# Optocoupler_STM32.net
KiCad netlist of a schematic drawn in Altium Designer
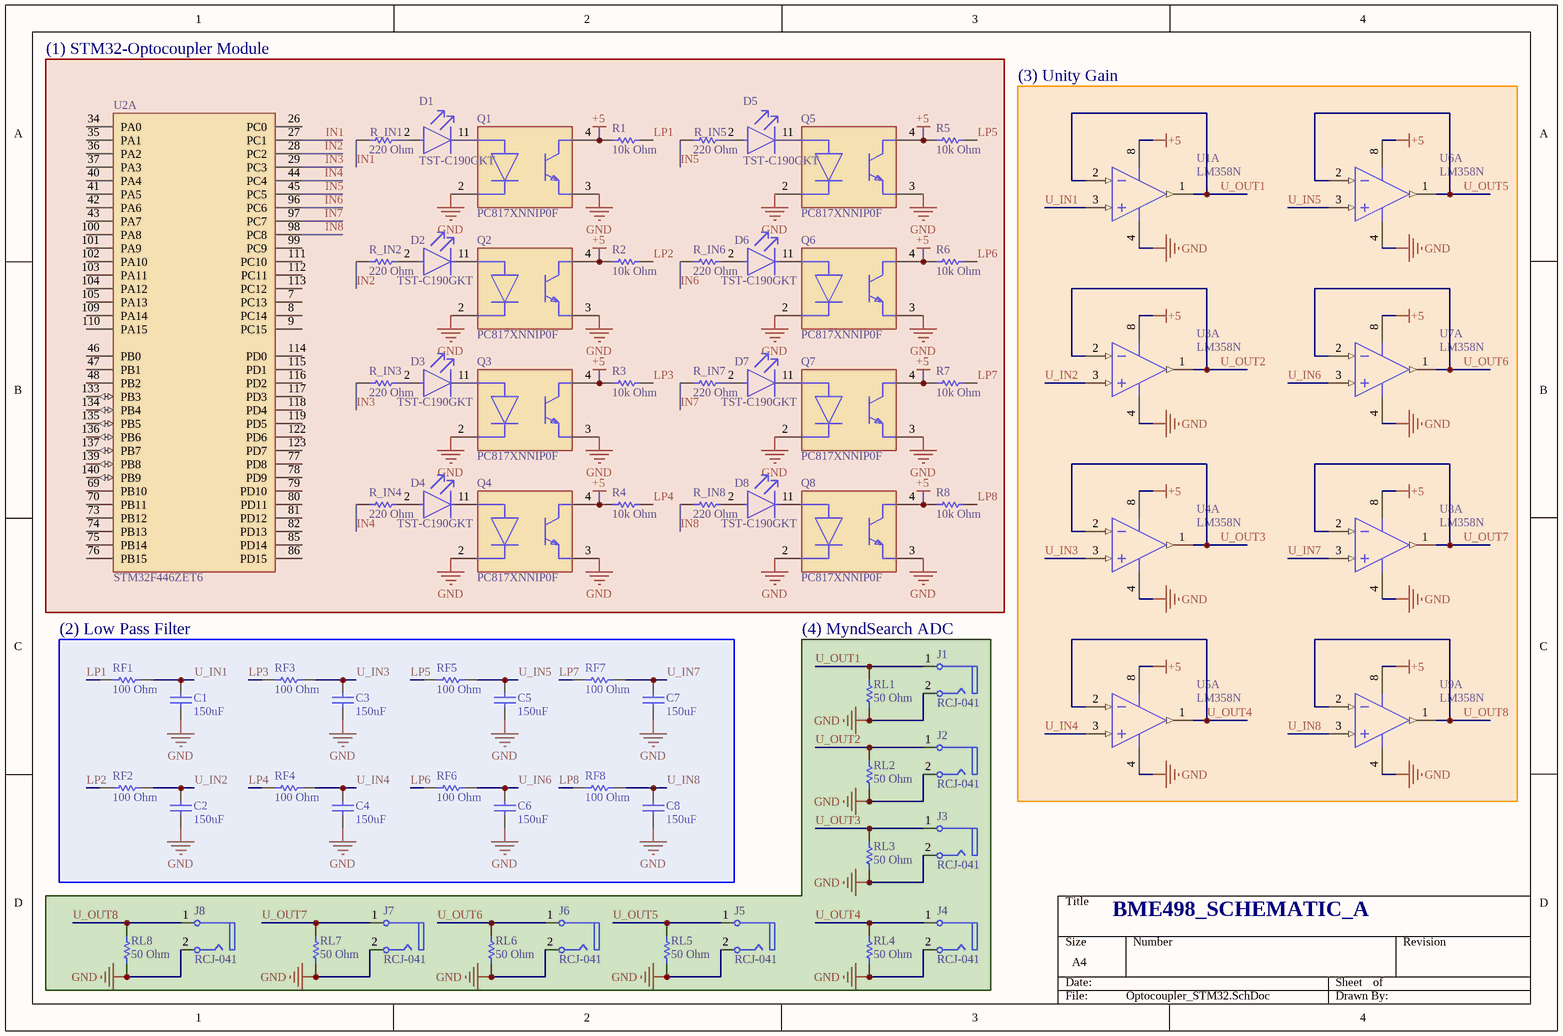
[diagram p0: Optocoupler_STM32.SchDoc]

(export (version "E")
  (design (tool "Eeschema 10.0.6"))
  (components
    (comp (ref "C1")
      (value "150uF")
      (footprint "RADIAL-0.1")
      (description "Capacitor")
      (fields
        (field (name "MANUFACTURER PART NUMBER") "EEA-GA1C150B")
        (field (name "PUBLISHER") "Altium Limited")
      )
      (libsource (lib "ECE295-Capacitors-TH") (part "CAP ALUM 15UF 20% 16V RADIAL"))
    )
    (comp (ref "C2")
      (value "150uF")
      (footprint "RADIAL-0.1")
      (description "Capacitor")
      (fields
        (field (name "MANUFACTURER PART NUMBER") "EEA-GA1C150B")
        (field (name "PUBLISHER") "Altium Limited")
      )
      (libsource (lib "ECE295-Capacitors-TH") (part "CAP ALUM 15UF 20% 16V RADIAL"))
    )
    (comp (ref "C3")
      (value "150uF")
      (footprint "RADIAL-0.1")
      (description "Capacitor")
      (fields
        (field (name "MANUFACTURER PART NUMBER") "EEA-GA1C150B")
        (field (name "PUBLISHER") "Altium Limited")
      )
      (libsource (lib "ECE295-Capacitors-TH") (part "CAP ALUM 15UF 20% 16V RADIAL"))
    )
    (comp (ref "C4")
      (value "150uF")
      (footprint "RADIAL-0.1")
      (description "Capacitor")
      (fields
        (field (name "MANUFACTURER PART NUMBER") "EEA-GA1C150B")
        (field (name "PUBLISHER") "Altium Limited")
      )
      (libsource (lib "ECE295-Capacitors-TH") (part "CAP ALUM 15UF 20% 16V RADIAL"))
    )
    (comp (ref "C5")
      (value "150uF")
      (footprint "RADIAL-0.1")
      (description "Capacitor")
      (fields
        (field (name "MANUFACTURER PART NUMBER") "EEA-GA1C150B")
        (field (name "PUBLISHER") "Altium Limited")
      )
      (libsource (lib "ECE295-Capacitors-TH") (part "CAP ALUM 15UF 20% 16V RADIAL"))
    )
    (comp (ref "C6")
      (value "150uF")
      (footprint "RADIAL-0.1")
      (description "Capacitor")
      (fields
        (field (name "MANUFACTURER PART NUMBER") "EEA-GA1C150B")
        (field (name "PUBLISHER") "Altium Limited")
      )
      (libsource (lib "ECE295-Capacitors-TH") (part "CAP ALUM 15UF 20% 16V RADIAL"))
    )
    (comp (ref "C7")
      (value "150uF")
      (footprint "RADIAL-0.1")
      (description "Capacitor")
      (fields
        (field (name "MANUFACTURER PART NUMBER") "EEA-GA1C150B")
        (field (name "PUBLISHER") "Altium Limited")
      )
      (libsource (lib "ECE295-Capacitors-TH") (part "CAP ALUM 15UF 20% 16V RADIAL"))
    )
    (comp (ref "C8")
      (value "150uF")
      (footprint "RADIAL-0.1")
      (description "Capacitor")
      (fields
        (field (name "MANUFACTURER PART NUMBER") "EEA-GA1C150B")
        (field (name "PUBLISHER") "Altium Limited")
      )
      (libsource (lib "ECE295-Capacitors-TH") (part "CAP ALUM 15UF 20% 16V RADIAL"))
    )
    (comp (ref "D1")
      (value "TST-C190GKT")
      (footprint "FP-LTST-C190GKT-MFG")
      (description "LED GREEN CLEAR CHIP SMD")
      (fields (field (name "VOLTAGE") "2V"))
      (libsource (lib "Altium Content Vault") (part "8706943c75ba83719d021d2fdc84c58"))
    )
    (comp (ref "D2")
      (value "TST-C190GKT")
      (footprint "FP-LTST-C190GKT-MFG")
      (description "LED GREEN CLEAR CHIP SMD")
      (fields (field (name "VOLTAGE") "2V"))
      (libsource (lib "Altium Content Vault") (part "8706943c75ba83719d021d2fdc84c58"))
    )
    (comp (ref "D3")
      (value "TST-C190GKT")
      (footprint "FP-LTST-C190GKT-MFG")
      (description "LED GREEN CLEAR CHIP SMD")
      (fields (field (name "VOLTAGE") "2V"))
      (libsource (lib "Altium Content Vault") (part "8706943c75ba83719d021d2fdc84c58"))
    )
    (comp (ref "D4")
      (value "TST-C190GKT")
      (footprint "FP-LTST-C190GKT-MFG")
      (description "LED GREEN CLEAR CHIP SMD")
      (fields (field (name "VOLTAGE") "2V"))
      (libsource (lib "Altium Content Vault") (part "8706943c75ba83719d021d2fdc84c58"))
    )
    (comp (ref "D5")
      (value "TST-C190GKT")
      (footprint "FP-LTST-C190GKT-MFG")
      (description "LED GREEN CLEAR CHIP SMD")
      (fields (field (name "VOLTAGE") "2V"))
      (libsource (lib "Altium Content Vault") (part "8706943c75ba83719d021d2fdc84c58"))
    )
    (comp (ref "D6")
      (value "TST-C190GKT")
      (footprint "FP-LTST-C190GKT-MFG")
      (description "LED GREEN CLEAR CHIP SMD")
      (fields (field (name "VOLTAGE") "2V"))
      (libsource (lib "Altium Content Vault") (part "8706943c75ba83719d021d2fdc84c58"))
    )
    (comp (ref "D7")
      (value "TST-C190GKT")
      (footprint "FP-LTST-C190GKT-MFG")
      (description "LED GREEN CLEAR CHIP SMD")
      (fields (field (name "VOLTAGE") "2V"))
      (libsource (lib "Altium Content Vault") (part "8706943c75ba83719d021d2fdc84c58"))
    )
    (comp (ref "D8")
      (value "TST-C190GKT")
      (footprint "FP-LTST-C190GKT-MFG")
      (description "LED GREEN CLEAR CHIP SMD")
      (fields (field (name "VOLTAGE") "2V"))
      (libsource (lib "Altium Content Vault") (part "8706943c75ba83719d021d2fdc84c58"))
    )
    (comp (ref "J1")
      (value "RCJ-041")
      (footprint "CUI-RCJ-041_V")
      (description "Female RCJ Jack, 2 Position, Height 11.724 mm, Tail Length 4 mm, RoHS, Bulk")
      (libsource (lib "Altium Content Vault") (part "JACK-2CD2"))
    )
    (comp (ref "J2")
      (value "RCJ-041")
      (footprint "CUI-RCJ-041_V")
      (description "Female RCJ Jack, 2 Position, Height 11.724 mm, Tail Length 4 mm, RoHS, Bulk")
      (libsource (lib "Altium Content Vault") (part "JACK-2CD2"))
    )
    (comp (ref "J3")
      (value "RCJ-041")
      (footprint "CUI-RCJ-041_V")
      (description "Female RCJ Jack, 2 Position, Height 11.724 mm, Tail Length 4 mm, RoHS, Bulk")
      (libsource (lib "Altium Content Vault") (part "JACK-2CD2"))
    )
    (comp (ref "J4")
      (value "RCJ-041")
      (footprint "CUI-RCJ-041_V")
      (description "Female RCJ Jack, 2 Position, Height 11.724 mm, Tail Length 4 mm, RoHS, Bulk")
      (libsource (lib "Altium Content Vault") (part "JACK-2CD2"))
    )
    (comp (ref "J5")
      (value "RCJ-041")
      (footprint "CUI-RCJ-041_V")
      (description "Female RCJ Jack, 2 Position, Height 11.724 mm, Tail Length 4 mm, RoHS, Bulk")
      (libsource (lib "Altium Content Vault") (part "JACK-2CD2"))
    )
    (comp (ref "J6")
      (value "RCJ-041")
      (footprint "CUI-RCJ-041_V")
      (description "Female RCJ Jack, 2 Position, Height 11.724 mm, Tail Length 4 mm, RoHS, Bulk")
      (libsource (lib "Altium Content Vault") (part "JACK-2CD2"))
    )
    (comp (ref "J7")
      (value "RCJ-041")
      (footprint "CUI-RCJ-041_V")
      (description "Female RCJ Jack, 2 Position, Height 11.724 mm, Tail Length 4 mm, RoHS, Bulk")
      (libsource (lib "Altium Content Vault") (part "JACK-2CD2"))
    )
    (comp (ref "J8")
      (value "RCJ-041")
      (footprint "CUI-RCJ-041_V")
      (description "Female RCJ Jack, 2 Position, Height 11.724 mm, Tail Length 4 mm, RoHS, Bulk")
      (libsource (lib "Altium Content Vault") (part "JACK-2CD2"))
    )
    (comp (ref "Q1")
      (value "PC817XNNIP0F")
      (footprint "FP-PC817XNNIP0F-MFG")
      (description "OPTOISOLATOR 5KV TRANS 4SMD")
      (libsource (lib "Altium Content Vault") (part "6470904bf6395c62928ee73e60120b8"))
    )
    (comp (ref "Q2")
      (value "PC817XNNIP0F")
      (footprint "FP-PC817XNNIP0F-MFG")
      (description "OPTOISOLATOR 5KV TRANS 4SMD")
      (libsource (lib "Altium Content Vault") (part "6470904bf6395c62928ee73e60120b8"))
    )
    (comp (ref "Q3")
      (value "PC817XNNIP0F")
      (footprint "FP-PC817XNNIP0F-MFG")
      (description "OPTOISOLATOR 5KV TRANS 4SMD")
      (libsource (lib "Altium Content Vault") (part "6470904bf6395c62928ee73e60120b8"))
    )
    (comp (ref "Q4")
      (value "PC817XNNIP0F")
      (footprint "FP-PC817XNNIP0F-MFG")
      (description "OPTOISOLATOR 5KV TRANS 4SMD")
      (libsource (lib "Altium Content Vault") (part "6470904bf6395c62928ee73e60120b8"))
    )
    (comp (ref "Q5")
      (value "PC817XNNIP0F")
      (footprint "FP-PC817XNNIP0F-MFG")
      (description "OPTOISOLATOR 5KV TRANS 4SMD")
      (libsource (lib "Altium Content Vault") (part "6470904bf6395c62928ee73e60120b8"))
    )
    (comp (ref "Q6")
      (value "PC817XNNIP0F")
      (footprint "FP-PC817XNNIP0F-MFG")
      (description "OPTOISOLATOR 5KV TRANS 4SMD")
      (libsource (lib "Altium Content Vault") (part "6470904bf6395c62928ee73e60120b8"))
    )
    (comp (ref "Q7")
      (value "PC817XNNIP0F")
      (footprint "FP-PC817XNNIP0F-MFG")
      (description "OPTOISOLATOR 5KV TRANS 4SMD")
      (libsource (lib "Altium Content Vault") (part "6470904bf6395c62928ee73e60120b8"))
    )
    (comp (ref "Q8")
      (value "PC817XNNIP0F")
      (footprint "FP-PC817XNNIP0F-MFG")
      (description "OPTOISOLATOR 5KV TRANS 4SMD")
      (libsource (lib "Altium Content Vault") (part "6470904bf6395c62928ee73e60120b8"))
    )
    (comp (ref "R1")
      (value "10k Ohm")
      (footprint "AXIAL-0.3")
      (description "Resistor")
      (fields
        (field (name "MANUFACTURER PART NUMBER") "CFR-25JB-52-10R")
        (field (name "TOLERANCE") "0.05")
        (field (name "PUBLISHER") "Altium Limited")
      )
      (libsource (lib "ECE295-Resistors-TH") (part "RES 10 OHM 5% 1/4W AXIAL"))
    )
    (comp (ref "R2")
      (value "10k Ohm")
      (footprint "AXIAL-0.3")
      (description "Resistor")
      (fields
        (field (name "MANUFACTURER PART NUMBER") "CFR-25JB-52-10R")
        (field (name "TOLERANCE") "0.05")
        (field (name "PUBLISHER") "Altium Limited")
      )
      (libsource (lib "ECE295-Resistors-TH") (part "RES 10 OHM 5% 1/4W AXIAL"))
    )
    (comp (ref "R3")
      (value "10k Ohm")
      (footprint "AXIAL-0.3")
      (description "Resistor")
      (fields
        (field (name "MANUFACTURER PART NUMBER") "CFR-25JB-52-10R")
        (field (name "TOLERANCE") "0.05")
        (field (name "PUBLISHER") "Altium Limited")
      )
      (libsource (lib "ECE295-Resistors-TH") (part "RES 10 OHM 5% 1/4W AXIAL"))
    )
    (comp (ref "R4")
      (value "10k Ohm")
      (footprint "AXIAL-0.3")
      (description "Resistor")
      (fields
        (field (name "MANUFACTURER PART NUMBER") "CFR-25JB-52-10R")
        (field (name "TOLERANCE") "0.05")
        (field (name "PUBLISHER") "Altium Limited")
      )
      (libsource (lib "ECE295-Resistors-TH") (part "RES 10 OHM 5% 1/4W AXIAL"))
    )
    (comp (ref "R5")
      (value "10k Ohm")
      (footprint "AXIAL-0.3")
      (description "Resistor")
      (fields
        (field (name "MANUFACTURER PART NUMBER") "CFR-25JB-52-10R")
        (field (name "TOLERANCE") "0.05")
        (field (name "PUBLISHER") "Altium Limited")
      )
      (libsource (lib "ECE295-Resistors-TH") (part "RES 10 OHM 5% 1/4W AXIAL"))
    )
    (comp (ref "R6")
      (value "10k Ohm")
      (footprint "AXIAL-0.3")
      (description "Resistor")
      (fields
        (field (name "MANUFACTURER PART NUMBER") "CFR-25JB-52-10R")
        (field (name "TOLERANCE") "0.05")
        (field (name "PUBLISHER") "Altium Limited")
      )
      (libsource (lib "ECE295-Resistors-TH") (part "RES 10 OHM 5% 1/4W AXIAL"))
    )
    (comp (ref "R7")
      (value "10k Ohm")
      (footprint "AXIAL-0.3")
      (description "Resistor")
      (fields
        (field (name "MANUFACTURER PART NUMBER") "CFR-25JB-52-10R")
        (field (name "TOLERANCE") "0.05")
        (field (name "PUBLISHER") "Altium Limited")
      )
      (libsource (lib "ECE295-Resistors-TH") (part "RES 10 OHM 5% 1/4W AXIAL"))
    )
    (comp (ref "R8")
      (value "10k Ohm")
      (footprint "AXIAL-0.3")
      (description "Resistor")
      (fields
        (field (name "MANUFACTURER PART NUMBER") "CFR-25JB-52-10R")
        (field (name "TOLERANCE") "0.05")
        (field (name "PUBLISHER") "Altium Limited")
      )
      (libsource (lib "ECE295-Resistors-TH") (part "RES 10 OHM 5% 1/4W AXIAL"))
    )
    (comp (ref "RF1")
      (value "100 Ohm")
      (footprint "AXIAL-0.3")
      (description "Resistor")
      (fields
        (field (name "MANUFACTURER PART NUMBER") "CFR-25JB-52-10R")
        (field (name "TOLERANCE") "0.05")
        (field (name "PUBLISHER") "Altium Limited")
      )
      (libsource (lib "ECE295-Resistors-TH") (part "RES 10 OHM 5% 1/4W AXIAL"))
    )
    (comp (ref "RF2")
      (value "100 Ohm")
      (footprint "AXIAL-0.3")
      (description "Resistor")
      (fields
        (field (name "MANUFACTURER PART NUMBER") "CFR-25JB-52-10R")
        (field (name "TOLERANCE") "0.05")
        (field (name "PUBLISHER") "Altium Limited")
      )
      (libsource (lib "ECE295-Resistors-TH") (part "RES 10 OHM 5% 1/4W AXIAL"))
    )
    (comp (ref "RF3")
      (value "100 Ohm")
      (footprint "AXIAL-0.3")
      (description "Resistor")
      (fields
        (field (name "MANUFACTURER PART NUMBER") "CFR-25JB-52-10R")
        (field (name "TOLERANCE") "0.05")
        (field (name "PUBLISHER") "Altium Limited")
      )
      (libsource (lib "ECE295-Resistors-TH") (part "RES 10 OHM 5% 1/4W AXIAL"))
    )
    (comp (ref "RF4")
      (value "100 Ohm")
      (footprint "AXIAL-0.3")
      (description "Resistor")
      (fields
        (field (name "MANUFACTURER PART NUMBER") "CFR-25JB-52-10R")
        (field (name "TOLERANCE") "0.05")
        (field (name "PUBLISHER") "Altium Limited")
      )
      (libsource (lib "ECE295-Resistors-TH") (part "RES 10 OHM 5% 1/4W AXIAL"))
    )
    (comp (ref "RF5")
      (value "100 Ohm")
      (footprint "AXIAL-0.3")
      (description "Resistor")
      (fields
        (field (name "MANUFACTURER PART NUMBER") "CFR-25JB-52-10R")
        (field (name "TOLERANCE") "0.05")
        (field (name "PUBLISHER") "Altium Limited")
      )
      (libsource (lib "ECE295-Resistors-TH") (part "RES 10 OHM 5% 1/4W AXIAL"))
    )
    (comp (ref "RF6")
      (value "100 Ohm")
      (footprint "AXIAL-0.3")
      (description "Resistor")
      (fields
        (field (name "MANUFACTURER PART NUMBER") "CFR-25JB-52-10R")
        (field (name "TOLERANCE") "0.05")
        (field (name "PUBLISHER") "Altium Limited")
      )
      (libsource (lib "ECE295-Resistors-TH") (part "RES 10 OHM 5% 1/4W AXIAL"))
    )
    (comp (ref "RF7")
      (value "100 Ohm")
      (footprint "AXIAL-0.3")
      (description "Resistor")
      (fields
        (field (name "MANUFACTURER PART NUMBER") "CFR-25JB-52-10R")
        (field (name "TOLERANCE") "0.05")
        (field (name "PUBLISHER") "Altium Limited")
      )
      (libsource (lib "ECE295-Resistors-TH") (part "RES 10 OHM 5% 1/4W AXIAL"))
    )
    (comp (ref "RF8")
      (value "100 Ohm")
      (footprint "AXIAL-0.3")
      (description "Resistor")
      (fields
        (field (name "MANUFACTURER PART NUMBER") "CFR-25JB-52-10R")
        (field (name "TOLERANCE") "0.05")
        (field (name "PUBLISHER") "Altium Limited")
      )
      (libsource (lib "ECE295-Resistors-TH") (part "RES 10 OHM 5% 1/4W AXIAL"))
    )
    (comp (ref "RL1")
      (value "50 Ohm")
      (footprint "AXIAL-0.3")
      (description "Resistor")
      (fields
        (field (name "MANUFACTURER PART NUMBER") "CFR-25JB-52-10R")
        (field (name "TOLERANCE") "0.05")
        (field (name "PUBLISHER") "Altium Limited")
      )
      (libsource (lib "ECE295-Resistors-TH") (part "RES 10 OHM 5% 1/4W AXIAL"))
    )
    (comp (ref "RL2")
      (value "50 Ohm")
      (footprint "AXIAL-0.3")
      (description "Resistor")
      (fields
        (field (name "MANUFACTURER PART NUMBER") "CFR-25JB-52-10R")
        (field (name "TOLERANCE") "0.05")
        (field (name "PUBLISHER") "Altium Limited")
      )
      (libsource (lib "ECE295-Resistors-TH") (part "RES 10 OHM 5% 1/4W AXIAL"))
    )
    (comp (ref "RL3")
      (value "50 Ohm")
      (footprint "AXIAL-0.3")
      (description "Resistor")
      (fields
        (field (name "MANUFACTURER PART NUMBER") "CFR-25JB-52-10R")
        (field (name "TOLERANCE") "0.05")
        (field (name "PUBLISHER") "Altium Limited")
      )
      (libsource (lib "ECE295-Resistors-TH") (part "RES 10 OHM 5% 1/4W AXIAL"))
    )
    (comp (ref "RL4")
      (value "50 Ohm")
      (footprint "AXIAL-0.3")
      (description "Resistor")
      (fields
        (field (name "MANUFACTURER PART NUMBER") "CFR-25JB-52-10R")
        (field (name "TOLERANCE") "0.05")
        (field (name "PUBLISHER") "Altium Limited")
      )
      (libsource (lib "ECE295-Resistors-TH") (part "RES 10 OHM 5% 1/4W AXIAL"))
    )
    (comp (ref "RL5")
      (value "50 Ohm")
      (footprint "AXIAL-0.3")
      (description "Resistor")
      (fields
        (field (name "MANUFACTURER PART NUMBER") "CFR-25JB-52-10R")
        (field (name "TOLERANCE") "0.05")
        (field (name "PUBLISHER") "Altium Limited")
      )
      (libsource (lib "ECE295-Resistors-TH") (part "RES 10 OHM 5% 1/4W AXIAL"))
    )
    (comp (ref "RL6")
      (value "50 Ohm")
      (footprint "AXIAL-0.3")
      (description "Resistor")
      (fields
        (field (name "MANUFACTURER PART NUMBER") "CFR-25JB-52-10R")
        (field (name "TOLERANCE") "0.05")
        (field (name "PUBLISHER") "Altium Limited")
      )
      (libsource (lib "ECE295-Resistors-TH") (part "RES 10 OHM 5% 1/4W AXIAL"))
    )
    (comp (ref "RL7")
      (value "50 Ohm")
      (footprint "AXIAL-0.3")
      (description "Resistor")
      (fields
        (field (name "MANUFACTURER PART NUMBER") "CFR-25JB-52-10R")
        (field (name "TOLERANCE") "0.05")
        (field (name "PUBLISHER") "Altium Limited")
      )
      (libsource (lib "ECE295-Resistors-TH") (part "RES 10 OHM 5% 1/4W AXIAL"))
    )
    (comp (ref "RL8")
      (value "50 Ohm")
      (footprint "AXIAL-0.3")
      (description "Resistor")
      (fields
        (field (name "MANUFACTURER PART NUMBER") "CFR-25JB-52-10R")
        (field (name "TOLERANCE") "0.05")
        (field (name "PUBLISHER") "Altium Limited")
      )
      (libsource (lib "ECE295-Resistors-TH") (part "RES 10 OHM 5% 1/4W AXIAL"))
    )
    (comp (ref "R_IN1")
      (value "220 Ohm")
      (footprint "AXIAL-0.3")
      (description "Resistor")
      (fields
        (field (name "MANUFACTURER PART NUMBER") "CFR-25JB-52-10R")
        (field (name "TOLERANCE") "0.05")
        (field (name "PUBLISHER") "Altium Limited")
      )
      (libsource (lib "ECE295-Resistors-TH") (part "RES 10 OHM 5% 1/4W AXIAL"))
    )
    (comp (ref "R_IN2")
      (value "220 Ohm")
      (footprint "AXIAL-0.3")
      (description "Resistor")
      (fields
        (field (name "MANUFACTURER PART NUMBER") "CFR-25JB-52-10R")
        (field (name "TOLERANCE") "0.05")
        (field (name "PUBLISHER") "Altium Limited")
      )
      (libsource (lib "ECE295-Resistors-TH") (part "RES 10 OHM 5% 1/4W AXIAL"))
    )
    (comp (ref "R_IN3")
      (value "220 Ohm")
      (footprint "AXIAL-0.3")
      (description "Resistor")
      (fields
        (field (name "MANUFACTURER PART NUMBER") "CFR-25JB-52-10R")
        (field (name "TOLERANCE") "0.05")
        (field (name "PUBLISHER") "Altium Limited")
      )
      (libsource (lib "ECE295-Resistors-TH") (part "RES 10 OHM 5% 1/4W AXIAL"))
    )
    (comp (ref "R_IN4")
      (value "220 Ohm")
      (footprint "AXIAL-0.3")
      (description "Resistor")
      (fields
        (field (name "MANUFACTURER PART NUMBER") "CFR-25JB-52-10R")
        (field (name "TOLERANCE") "0.05")
        (field (name "PUBLISHER") "Altium Limited")
      )
      (libsource (lib "ECE295-Resistors-TH") (part "RES 10 OHM 5% 1/4W AXIAL"))
    )
    (comp (ref "R_IN5")
      (value "220 Ohm")
      (footprint "AXIAL-0.3")
      (description "Resistor")
      (fields
        (field (name "MANUFACTURER PART NUMBER") "CFR-25JB-52-10R")
        (field (name "TOLERANCE") "0.05")
        (field (name "PUBLISHER") "Altium Limited")
      )
      (libsource (lib "ECE295-Resistors-TH") (part "RES 10 OHM 5% 1/4W AXIAL"))
    )
    (comp (ref "R_IN6")
      (value "220 Ohm")
      (footprint "AXIAL-0.3")
      (description "Resistor")
      (fields
        (field (name "MANUFACTURER PART NUMBER") "CFR-25JB-52-10R")
        (field (name "TOLERANCE") "0.05")
        (field (name "PUBLISHER") "Altium Limited")
      )
      (libsource (lib "ECE295-Resistors-TH") (part "RES 10 OHM 5% 1/4W AXIAL"))
    )
    (comp (ref "R_IN7")
      (value "220 Ohm")
      (footprint "AXIAL-0.3")
      (description "Resistor")
      (fields
        (field (name "MANUFACTURER PART NUMBER") "CFR-25JB-52-10R")
        (field (name "TOLERANCE") "0.05")
        (field (name "PUBLISHER") "Altium Limited")
      )
      (libsource (lib "ECE295-Resistors-TH") (part "RES 10 OHM 5% 1/4W AXIAL"))
    )
    (comp (ref "R_IN8")
      (value "220 Ohm")
      (footprint "AXIAL-0.3")
      (description "Resistor")
      (fields
        (field (name "MANUFACTURER PART NUMBER") "CFR-25JB-52-10R")
        (field (name "TOLERANCE") "0.05")
        (field (name "PUBLISHER") "Altium Limited")
      )
      (libsource (lib "ECE295-Resistors-TH") (part "RES 10 OHM 5% 1/4W AXIAL"))
    )
    (comp (ref "U1")
      (value "LM358N")
      (footprint "ONSC-PDIP-8-626-05_M")
      (description "Single Supply Dual Operational Amplifier, 3 to 32 V, 0 to 70 degC, 8-Pin PDIP, Tube")
      (fields (field (name "MANUFACTURER") "On Semiconductor"))
      (libsource (lib "Altium Content Vault") (part "ONSC-LM358_NCV2904-8"))
    )
    (comp (ref "U2")
      (value "STM32F446ZET6")
      (footprint "FP-STM32F446ZET6-MFG")
      (description "IC MCU 32BIT 512KB FLASH 144LQFP")
      (fields
        (field (name "OCTOPART") "https://octopart.com/stm32f446zet6-stmicroelectronics-52642927")
        (field (name "MANUFACTURER") "STMicroelectronics")
      )
      (libsource (lib "Altium Content Vault") (part "a0fab8d4e0431f78458e0514a03e2d2"))
    )
    (comp (ref "U3")
      (value "LM358N")
      (footprint "ONSC-PDIP-8-626-05_M")
      (description "Single Supply Dual Operational Amplifier, 3 to 32 V, 0 to 70 degC, 8-Pin PDIP, Tube")
      (fields (field (name "MANUFACTURER") "On Semiconductor"))
      (libsource (lib "Altium Content Vault") (part "ONSC-LM358_NCV2904-8"))
    )
    (comp (ref "U4")
      (value "LM358N")
      (footprint "ONSC-PDIP-8-626-05_M")
      (description "Single Supply Dual Operational Amplifier, 3 to 32 V, 0 to 70 degC, 8-Pin PDIP, Tube")
      (fields (field (name "MANUFACTURER") "On Semiconductor"))
      (libsource (lib "Altium Content Vault") (part "ONSC-LM358_NCV2904-8"))
    )
    (comp (ref "U5")
      (value "LM358N")
      (footprint "ONSC-PDIP-8-626-05_M")
      (description "Single Supply Dual Operational Amplifier, 3 to 32 V, 0 to 70 degC, 8-Pin PDIP, Tube")
      (fields (field (name "MANUFACTURER") "On Semiconductor"))
      (libsource (lib "Altium Content Vault") (part "ONSC-LM358_NCV2904-8"))
    )
    (comp (ref "U6")
      (value "LM358N")
      (footprint "ONSC-PDIP-8-626-05_M")
      (description "Single Supply Dual Operational Amplifier, 3 to 32 V, 0 to 70 degC, 8-Pin PDIP, Tube")
      (fields (field (name "MANUFACTURER") "On Semiconductor"))
      (libsource (lib "Altium Content Vault") (part "ONSC-LM358_NCV2904-8"))
    )
    (comp (ref "U7")
      (value "LM358N")
      (footprint "ONSC-PDIP-8-626-05_M")
      (description "Single Supply Dual Operational Amplifier, 3 to 32 V, 0 to 70 degC, 8-Pin PDIP, Tube")
      (fields (field (name "MANUFACTURER") "On Semiconductor"))
      (libsource (lib "Altium Content Vault") (part "ONSC-LM358_NCV2904-8"))
    )
    (comp (ref "U8")
      (value "LM358N")
      (footprint "ONSC-PDIP-8-626-05_M")
      (description "Single Supply Dual Operational Amplifier, 3 to 32 V, 0 to 70 degC, 8-Pin PDIP, Tube")
      (fields (field (name "MANUFACTURER") "On Semiconductor"))
      (libsource (lib "Altium Content Vault") (part "ONSC-LM358_NCV2904-8"))
    )
    (comp (ref "U9")
      (value "LM358N")
      (footprint "ONSC-PDIP-8-626-05_M")
      (description "Single Supply Dual Operational Amplifier, 3 to 32 V, 0 to 70 degC, 8-Pin PDIP, Tube")
      (fields (field (name "MANUFACTURER") "On Semiconductor"))
      (libsource (lib "Altium Content Vault") (part "ONSC-LM358_NCV2904-8"))
    )
  )
  (nets
    (net (code "1") (name "+5") (class "Default")
      (node (ref "Q1") (pin "4") (pinfunction "C_4") (pintype "passive"))
      (node (ref "Q2") (pin "4") (pinfunction "C_4") (pintype "passive"))
      (node (ref "Q3") (pin "4") (pinfunction "C_4") (pintype "passive"))
      (node (ref "Q4") (pin "4") (pinfunction "C_4") (pintype "passive"))
      (node (ref "Q5") (pin "4") (pinfunction "C_4") (pintype "passive"))
      (node (ref "Q6") (pin "4") (pinfunction "C_4") (pintype "passive"))
      (node (ref "Q7") (pin "4") (pinfunction "C_4") (pintype "passive"))
      (node (ref "Q8") (pin "4") (pinfunction "C_4") (pintype "passive"))
      (node (ref "R1") (pin "1") (pinfunction "1_1") (pintype "passive"))
      (node (ref "R2") (pin "1") (pinfunction "1_1") (pintype "passive"))
      (node (ref "R3") (pin "1") (pinfunction "1_1") (pintype "passive"))
      (node (ref "R4") (pin "1") (pinfunction "1_1") (pintype "passive"))
      (node (ref "R5") (pin "1") (pinfunction "1_1") (pintype "passive"))
      (node (ref "R6") (pin "1") (pinfunction "1_1") (pintype "passive"))
      (node (ref "R7") (pin "1") (pinfunction "1_1") (pintype "passive"))
      (node (ref "R8") (pin "1") (pinfunction "1_1") (pintype "passive"))
      (node (ref "U1") (pin "8") (pinfunction "VCC_8") (pintype "power_in"))
      (node (ref "U3") (pin "8") (pinfunction "VCC_8") (pintype "power_in"))
      (node (ref "U4") (pin "8") (pinfunction "VCC_8") (pintype "power_in"))
      (node (ref "U5") (pin "8") (pinfunction "VCC_8") (pintype "power_in"))
      (node (ref "U6") (pin "8") (pinfunction "VCC_8") (pintype "power_in"))
      (node (ref "U7") (pin "8") (pinfunction "VCC_8") (pintype "power_in"))
      (node (ref "U8") (pin "8") (pinfunction "VCC_8") (pintype "power_in"))
      (node (ref "U9") (pin "8") (pinfunction "VCC_8") (pintype "power_in"))
    )
    (net (code "2") (name "/IN1") (class "Default")
      (node (ref "R_IN1") (pin "2") (pinfunction "2_2") (pintype "passive"))
      (node (ref "U2") (pin "27") (pinfunction "PC1_27") (pintype "passive"))
    )
    (net (code "3") (name "/IN2") (class "Default")
      (node (ref "R_IN2") (pin "2") (pinfunction "2_2") (pintype "passive"))
      (node (ref "U2") (pin "28") (pinfunction "PC2_28") (pintype "passive"))
    )
    (net (code "4") (name "/IN3") (class "Default")
      (node (ref "R_IN3") (pin "2") (pinfunction "2_2") (pintype "passive"))
      (node (ref "U2") (pin "29") (pinfunction "PC3_29") (pintype "passive"))
    )
    (net (code "5") (name "/IN4") (class "Default")
      (node (ref "R_IN4") (pin "2") (pinfunction "2_2") (pintype "passive"))
      (node (ref "U2") (pin "44") (pinfunction "PC4_44") (pintype "passive"))
    )
    (net (code "6") (name "/IN5") (class "Default")
      (node (ref "R_IN5") (pin "2") (pinfunction "2_2") (pintype "passive"))
      (node (ref "U2") (pin "45") (pinfunction "PC5_45") (pintype "passive"))
    )
    (net (code "7") (name "/IN6") (class "Default")
      (node (ref "R_IN6") (pin "2") (pinfunction "2_2") (pintype "passive"))
      (node (ref "U2") (pin "96") (pinfunction "PC6_96") (pintype "passive"))
    )
    (net (code "8") (name "/IN7") (class "Default")
      (node (ref "R_IN7") (pin "2") (pinfunction "2_2") (pintype "passive"))
      (node (ref "U2") (pin "97") (pinfunction "PC7_97") (pintype "passive"))
    )
    (net (code "9") (name "/IN8") (class "Default")
      (node (ref "R_IN8") (pin "2") (pinfunction "2_2") (pintype "passive"))
      (node (ref "U2") (pin "98") (pinfunction "PC8_98") (pintype "passive"))
    )
    (net (code "10") (name "/LP1") (class "Default")
      (node (ref "R1") (pin "2") (pinfunction "2_2") (pintype "passive"))
      (node (ref "RF1") (pin "1") (pinfunction "1_1") (pintype "passive"))
    )
    (net (code "11") (name "/LP2") (class "Default")
      (node (ref "R2") (pin "2") (pinfunction "2_2") (pintype "passive"))
      (node (ref "RF2") (pin "1") (pinfunction "1_1") (pintype "passive"))
    )
    (net (code "12") (name "/LP3") (class "Default")
      (node (ref "R3") (pin "2") (pinfunction "2_2") (pintype "passive"))
      (node (ref "RF3") (pin "1") (pinfunction "1_1") (pintype "passive"))
    )
    (net (code "13") (name "/LP4") (class "Default")
      (node (ref "R4") (pin "2") (pinfunction "2_2") (pintype "passive"))
      (node (ref "RF4") (pin "1") (pinfunction "1_1") (pintype "passive"))
    )
    (net (code "14") (name "/LP5") (class "Default")
      (node (ref "R5") (pin "2") (pinfunction "2_2") (pintype "passive"))
      (node (ref "RF5") (pin "1") (pinfunction "1_1") (pintype "passive"))
    )
    (net (code "15") (name "/LP6") (class "Default")
      (node (ref "R6") (pin "2") (pinfunction "2_2") (pintype "passive"))
      (node (ref "RF6") (pin "1") (pinfunction "1_1") (pintype "passive"))
    )
    (net (code "16") (name "/LP7") (class "Default")
      (node (ref "R7") (pin "2") (pinfunction "2_2") (pintype "passive"))
      (node (ref "RF7") (pin "1") (pinfunction "1_1") (pintype "passive"))
    )
    (net (code "17") (name "/LP8") (class "Default")
      (node (ref "R8") (pin "2") (pinfunction "2_2") (pintype "passive"))
      (node (ref "RF8") (pin "1") (pinfunction "1_1") (pintype "passive"))
    )
    (net (code "18") (name "/U_IN1") (class "Default")
      (node (ref "C1") (pin "2") (pinfunction "2_2") (pintype "passive"))
      (node (ref "RF1") (pin "2") (pinfunction "2_2") (pintype "passive"))
      (node (ref "U1") (pin "3") (pinfunction "INA+_3") (pintype "input"))
    )
    (net (code "19") (name "/U_IN2") (class "Default")
      (node (ref "C2") (pin "2") (pinfunction "2_2") (pintype "passive"))
      (node (ref "RF2") (pin "2") (pinfunction "2_2") (pintype "passive"))
      (node (ref "U3") (pin "3") (pinfunction "INA+_3") (pintype "input"))
    )
    (net (code "20") (name "/U_IN3") (class "Default")
      (node (ref "C3") (pin "2") (pinfunction "2_2") (pintype "passive"))
      (node (ref "RF3") (pin "2") (pinfunction "2_2") (pintype "passive"))
      (node (ref "U4") (pin "3") (pinfunction "INA+_3") (pintype "input"))
    )
    (net (code "21") (name "/U_IN4") (class "Default")
      (node (ref "C4") (pin "2") (pinfunction "2_2") (pintype "passive"))
      (node (ref "RF4") (pin "2") (pinfunction "2_2") (pintype "passive"))
      (node (ref "U5") (pin "3") (pinfunction "INA+_3") (pintype "input"))
    )
    (net (code "22") (name "/U_IN5") (class "Default")
      (node (ref "C5") (pin "2") (pinfunction "2_2") (pintype "passive"))
      (node (ref "RF5") (pin "2") (pinfunction "2_2") (pintype "passive"))
      (node (ref "U6") (pin "3") (pinfunction "INA+_3") (pintype "input"))
    )
    (net (code "23") (name "/U_IN6") (class "Default")
      (node (ref "C6") (pin "2") (pinfunction "2_2") (pintype "passive"))
      (node (ref "RF6") (pin "2") (pinfunction "2_2") (pintype "passive"))
      (node (ref "U7") (pin "3") (pinfunction "INA+_3") (pintype "input"))
    )
    (net (code "24") (name "/U_IN7") (class "Default")
      (node (ref "C7") (pin "2") (pinfunction "2_2") (pintype "passive"))
      (node (ref "RF7") (pin "2") (pinfunction "2_2") (pintype "passive"))
      (node (ref "U8") (pin "3") (pinfunction "INA+_3") (pintype "input"))
    )
    (net (code "25") (name "/U_IN8") (class "Default")
      (node (ref "C8") (pin "2") (pinfunction "2_2") (pintype "passive"))
      (node (ref "RF8") (pin "2") (pinfunction "2_2") (pintype "passive"))
      (node (ref "U9") (pin "3") (pinfunction "INA+_3") (pintype "input"))
    )
    (net (code "26") (name "/U_OUT1") (class "Default")
      (node (ref "J1") (pin "1") (pinfunction "1_1") (pintype "passive"))
      (node (ref "RL1") (pin "2") (pinfunction "2_2") (pintype "passive"))
      (node (ref "U1") (pin "1") (pinfunction "OUTA_1") (pintype "output"))
      (node (ref "U1") (pin "2") (pinfunction "INA-_2") (pintype "input"))
    )
    (net (code "27") (name "/U_OUT2") (class "Default")
      (node (ref "J2") (pin "1") (pinfunction "1_1") (pintype "passive"))
      (node (ref "RL2") (pin "2") (pinfunction "2_2") (pintype "passive"))
      (node (ref "U3") (pin "1") (pinfunction "OUTA_1") (pintype "output"))
      (node (ref "U3") (pin "2") (pinfunction "INA-_2") (pintype "input"))
    )
    (net (code "28") (name "/U_OUT3") (class "Default")
      (node (ref "J3") (pin "1") (pinfunction "1_1") (pintype "passive"))
      (node (ref "RL3") (pin "2") (pinfunction "2_2") (pintype "passive"))
      (node (ref "U4") (pin "1") (pinfunction "OUTA_1") (pintype "output"))
      (node (ref "U4") (pin "2") (pinfunction "INA-_2") (pintype "input"))
    )
    (net (code "29") (name "/U_OUT4") (class "Default")
      (node (ref "J4") (pin "1") (pinfunction "1_1") (pintype "passive"))
      (node (ref "RL4") (pin "2") (pinfunction "2_2") (pintype "passive"))
      (node (ref "U5") (pin "1") (pinfunction "OUTA_1") (pintype "output"))
      (node (ref "U5") (pin "2") (pinfunction "INA-_2") (pintype "input"))
    )
    (net (code "30") (name "/U_OUT5") (class "Default")
      (node (ref "J5") (pin "1") (pinfunction "1_1") (pintype "passive"))
      (node (ref "RL5") (pin "2") (pinfunction "2_2") (pintype "passive"))
      (node (ref "U6") (pin "1") (pinfunction "OUTA_1") (pintype "output"))
      (node (ref "U6") (pin "2") (pinfunction "INA-_2") (pintype "input"))
    )
    (net (code "31") (name "/U_OUT6") (class "Default")
      (node (ref "J6") (pin "1") (pinfunction "1_1") (pintype "passive"))
      (node (ref "RL6") (pin "2") (pinfunction "2_2") (pintype "passive"))
      (node (ref "U7") (pin "1") (pinfunction "OUTA_1") (pintype "output"))
      (node (ref "U7") (pin "2") (pinfunction "INA-_2") (pintype "input"))
    )
    (net (code "32") (name "/U_OUT7") (class "Default")
      (node (ref "J7") (pin "1") (pinfunction "1_1") (pintype "passive"))
      (node (ref "RL7") (pin "2") (pinfunction "2_2") (pintype "passive"))
      (node (ref "U8") (pin "1") (pinfunction "OUTA_1") (pintype "output"))
      (node (ref "U8") (pin "2") (pinfunction "INA-_2") (pintype "input"))
    )
    (net (code "33") (name "/U_OUT8") (class "Default")
      (node (ref "J8") (pin "1") (pinfunction "1_1") (pintype "passive"))
      (node (ref "RL8") (pin "2") (pinfunction "2_2") (pintype "passive"))
      (node (ref "U9") (pin "1") (pinfunction "OUTA_1") (pintype "output"))
      (node (ref "U9") (pin "2") (pinfunction "INA-_2") (pintype "input"))
    )
    (net (code "34") (name "GND") (class "Default")
      (node (ref "C1") (pin "1") (pinfunction "1_1") (pintype "passive"))
      (node (ref "C2") (pin "1") (pinfunction "1_1") (pintype "passive"))
      (node (ref "C3") (pin "1") (pinfunction "1_1") (pintype "passive"))
      (node (ref "C4") (pin "1") (pinfunction "1_1") (pintype "passive"))
      (node (ref "C5") (pin "1") (pinfunction "1_1") (pintype "passive"))
      (node (ref "C6") (pin "1") (pinfunction "1_1") (pintype "passive"))
      (node (ref "C7") (pin "1") (pinfunction "1_1") (pintype "passive"))
      (node (ref "C8") (pin "1") (pinfunction "1_1") (pintype "passive"))
      (node (ref "J1") (pin "2") (pinfunction "2_2") (pintype "passive"))
      (node (ref "J2") (pin "2") (pinfunction "2_2") (pintype "passive"))
      (node (ref "J3") (pin "2") (pinfunction "2_2") (pintype "passive"))
      (node (ref "J4") (pin "2") (pinfunction "2_2") (pintype "passive"))
      (node (ref "J5") (pin "2") (pinfunction "2_2") (pintype "passive"))
      (node (ref "J6") (pin "2") (pinfunction "2_2") (pintype "passive"))
      (node (ref "J7") (pin "2") (pinfunction "2_2") (pintype "passive"))
      (node (ref "J8") (pin "2") (pinfunction "2_2") (pintype "passive"))
      (node (ref "Q1") (pin "2") (pinfunction "C_2") (pintype "passive"))
      (node (ref "Q1") (pin "3") (pinfunction "E_3") (pintype "passive"))
      (node (ref "Q2") (pin "2") (pinfunction "C_2") (pintype "passive"))
      (node (ref "Q2") (pin "3") (pinfunction "E_3") (pintype "passive"))
      (node (ref "Q3") (pin "2") (pinfunction "C_2") (pintype "passive"))
      (node (ref "Q3") (pin "3") (pinfunction "E_3") (pintype "passive"))
      (node (ref "Q4") (pin "2") (pinfunction "C_2") (pintype "passive"))
      (node (ref "Q4") (pin "3") (pinfunction "E_3") (pintype "passive"))
      (node (ref "Q5") (pin "2") (pinfunction "C_2") (pintype "passive"))
      (node (ref "Q5") (pin "3") (pinfunction "E_3") (pintype "passive"))
      (node (ref "Q6") (pin "2") (pinfunction "C_2") (pintype "passive"))
      (node (ref "Q6") (pin "3") (pinfunction "E_3") (pintype "passive"))
      (node (ref "Q7") (pin "2") (pinfunction "C_2") (pintype "passive"))
      (node (ref "Q7") (pin "3") (pinfunction "E_3") (pintype "passive"))
      (node (ref "Q8") (pin "2") (pinfunction "C_2") (pintype "passive"))
      (node (ref "Q8") (pin "3") (pinfunction "E_3") (pintype "passive"))
      (node (ref "RL1") (pin "1") (pinfunction "1_1") (pintype "passive"))
      (node (ref "RL2") (pin "1") (pinfunction "1_1") (pintype "passive"))
      (node (ref "RL3") (pin "1") (pinfunction "1_1") (pintype "passive"))
      (node (ref "RL4") (pin "1") (pinfunction "1_1") (pintype "passive"))
      (node (ref "RL5") (pin "1") (pinfunction "1_1") (pintype "passive"))
      (node (ref "RL6") (pin "1") (pinfunction "1_1") (pintype "passive"))
      (node (ref "RL7") (pin "1") (pinfunction "1_1") (pintype "passive"))
      (node (ref "RL8") (pin "1") (pinfunction "1_1") (pintype "passive"))
      (node (ref "U1") (pin "4") (pinfunction "VEE/GND_4") (pintype "power_in"))
      (node (ref "U3") (pin "4") (pinfunction "VEE/GND_4") (pintype "power_in"))
      (node (ref "U4") (pin "4") (pinfunction "VEE/GND_4") (pintype "power_in"))
      (node (ref "U5") (pin "4") (pinfunction "VEE/GND_4") (pintype "power_in"))
      (node (ref "U6") (pin "4") (pinfunction "VEE/GND_4") (pintype "power_in"))
      (node (ref "U7") (pin "4") (pinfunction "VEE/GND_4") (pintype "power_in"))
      (node (ref "U8") (pin "4") (pinfunction "VEE/GND_4") (pintype "power_in"))
      (node (ref "U9") (pin "4") (pinfunction "VEE/GND_4") (pintype "power_in"))
    )
    (net (code "35") (name "Net-(D1-A)") (class "Default")
      (node (ref "D1") (pin "2") (pinfunction "A_2") (pintype "passive"))
      (node (ref "R_IN1") (pin "1") (pinfunction "1_1") (pintype "passive"))
    )
    (net (code "36") (name "Net-(D1-C)") (class "Default")
      (node (ref "D1") (pin "1") (pinfunction "C_1") (pintype "passive"))
      (node (ref "Q1") (pin "1") (pinfunction "A_1") (pintype "passive"))
    )
    (net (code "37") (name "Net-(D3-A)") (class "Default")
      (node (ref "D3") (pin "2") (pinfunction "A_2") (pintype "passive"))
      (node (ref "R_IN3") (pin "1") (pinfunction "1_1") (pintype "passive"))
    )
    (net (code "38") (name "Net-(D3-C)") (class "Default")
      (node (ref "D3") (pin "1") (pinfunction "C_1") (pintype "passive"))
      (node (ref "Q3") (pin "1") (pinfunction "A_1") (pintype "passive"))
    )
    (net (code "39") (name "Net-(D5-A)") (class "Default")
      (node (ref "D5") (pin "2") (pinfunction "A_2") (pintype "passive"))
      (node (ref "R_IN5") (pin "1") (pinfunction "1_1") (pintype "passive"))
    )
    (net (code "40") (name "Net-(D5-C)") (class "Default")
      (node (ref "D5") (pin "1") (pinfunction "C_1") (pintype "passive"))
      (node (ref "Q5") (pin "1") (pinfunction "A_1") (pintype "passive"))
    )
    (net (code "41") (name "Net-(D7-A)") (class "Default")
      (node (ref "D7") (pin "2") (pinfunction "A_2") (pintype "passive"))
      (node (ref "R_IN7") (pin "1") (pinfunction "1_1") (pintype "passive"))
    )
    (net (code "42") (name "Net-(D7-C)") (class "Default")
      (node (ref "D7") (pin "1") (pinfunction "C_1") (pintype "passive"))
      (node (ref "Q7") (pin "1") (pinfunction "A_1") (pintype "passive"))
    )
    (net (code "43") (name "unconnected-(D2-A-Pad2)") (class "Default")
      (node (ref "D2") (pin "2") (pinfunction "A_2") (pintype "passive"))
    )
    (net (code "44") (name "unconnected-(D2-C-Pad1)") (class "Default")
      (node (ref "D2") (pin "1") (pinfunction "C_1") (pintype "passive"))
    )
    (net (code "45") (name "unconnected-(D4-A-Pad2)") (class "Default")
      (node (ref "D4") (pin "2") (pinfunction "A_2") (pintype "passive"))
    )
    (net (code "46") (name "unconnected-(D4-C-Pad1)") (class "Default")
      (node (ref "D4") (pin "1") (pinfunction "C_1") (pintype "passive"))
    )
    (net (code "47") (name "unconnected-(D6-A-Pad2)") (class "Default")
      (node (ref "D6") (pin "2") (pinfunction "A_2") (pintype "passive"))
    )
    (net (code "48") (name "unconnected-(D6-C-Pad1)") (class "Default")
      (node (ref "D6") (pin "1") (pinfunction "C_1") (pintype "passive"))
    )
    (net (code "49") (name "unconnected-(D8-A-Pad2)") (class "Default")
      (node (ref "D8") (pin "2") (pinfunction "A_2") (pintype "passive"))
    )
    (net (code "50") (name "unconnected-(D8-C-Pad1)") (class "Default")
      (node (ref "D8") (pin "1") (pinfunction "C_1") (pintype "passive"))
    )
    (net (code "51") (name "unconnected-(Q2-A-Pad1)") (class "Default")
      (node (ref "Q2") (pin "1") (pinfunction "A_1") (pintype "passive"))
    )
    (net (code "52") (name "unconnected-(Q4-A-Pad1)") (class "Default")
      (node (ref "Q4") (pin "1") (pinfunction "A_1") (pintype "passive"))
    )
    (net (code "53") (name "unconnected-(Q6-A-Pad1)") (class "Default")
      (node (ref "Q6") (pin "1") (pinfunction "A_1") (pintype "passive"))
    )
    (net (code "54") (name "unconnected-(Q8-A-Pad1)") (class "Default")
      (node (ref "Q8") (pin "1") (pinfunction "A_1") (pintype "passive"))
    )
    (net (code "55") (name "unconnected-(R_IN2-Pad1)") (class "Default")
      (node (ref "R_IN2") (pin "1") (pinfunction "1_1") (pintype "passive"))
    )
    (net (code "56") (name "unconnected-(R_IN4-Pad1)") (class "Default")
      (node (ref "R_IN4") (pin "1") (pinfunction "1_1") (pintype "passive"))
    )
    (net (code "57") (name "unconnected-(R_IN6-Pad1)") (class "Default")
      (node (ref "R_IN6") (pin "1") (pinfunction "1_1") (pintype "passive"))
    )
    (net (code "58") (name "unconnected-(R_IN8-Pad1)") (class "Default")
      (node (ref "R_IN8") (pin "1") (pinfunction "1_1") (pintype "passive"))
    )
    (net (code "59") (name "unconnected-(U2A-PA0-Pad34)") (class "Default")
      (node (ref "U2") (pin "34") (pinfunction "PA0_34") (pintype "passive"))
    )
    (net (code "60") (name "unconnected-(U2A-PA1-Pad35)") (class "Default")
      (node (ref "U2") (pin "35") (pinfunction "PA1_35") (pintype "passive"))
    )
    (net (code "61") (name "unconnected-(U2A-PA2-Pad36)") (class "Default")
      (node (ref "U2") (pin "36") (pinfunction "PA2_36") (pintype "passive"))
    )
    (net (code "62") (name "unconnected-(U2A-PA3-Pad37)") (class "Default")
      (node (ref "U2") (pin "37") (pinfunction "PA3_37") (pintype "passive"))
    )
    (net (code "63") (name "unconnected-(U2A-PA4-Pad40)") (class "Default")
      (node (ref "U2") (pin "40") (pinfunction "PA4_40") (pintype "passive"))
    )
    (net (code "64") (name "unconnected-(U2A-PA5-Pad41)") (class "Default")
      (node (ref "U2") (pin "41") (pinfunction "PA5_41") (pintype "passive"))
    )
    (net (code "65") (name "unconnected-(U2A-PA6-Pad42)") (class "Default")
      (node (ref "U2") (pin "42") (pinfunction "PA6_42") (pintype "passive"))
    )
    (net (code "66") (name "unconnected-(U2A-PA7-Pad43)") (class "Default")
      (node (ref "U2") (pin "43") (pinfunction "PA7_43") (pintype "passive"))
    )
    (net (code "67") (name "unconnected-(U2A-PA8-Pad100)") (class "Default")
      (node (ref "U2") (pin "100") (pinfunction "PA8_100") (pintype "passive"))
    )
    (net (code "68") (name "unconnected-(U2A-PA9-Pad101)") (class "Default")
      (node (ref "U2") (pin "101") (pinfunction "PA9_101") (pintype "passive"))
    )
    (net (code "69") (name "unconnected-(U2A-PA10-Pad102)") (class "Default")
      (node (ref "U2") (pin "102") (pinfunction "PA10_102") (pintype "passive"))
    )
    (net (code "70") (name "unconnected-(U2A-PA11-Pad103)") (class "Default")
      (node (ref "U2") (pin "103") (pinfunction "PA11_103") (pintype "passive"))
    )
    (net (code "71") (name "unconnected-(U2A-PA12-Pad104)") (class "Default")
      (node (ref "U2") (pin "104") (pinfunction "PA12_104") (pintype "passive"))
    )
    (net (code "72") (name "unconnected-(U2A-PA13-Pad105)") (class "Default")
      (node (ref "U2") (pin "105") (pinfunction "PA13_105") (pintype "passive"))
    )
    (net (code "73") (name "unconnected-(U2A-PA14-Pad109)") (class "Default")
      (node (ref "U2") (pin "109") (pinfunction "PA14_109") (pintype "passive"))
    )
    (net (code "74") (name "unconnected-(U2A-PA15-Pad110)") (class "Default")
      (node (ref "U2") (pin "110") (pinfunction "PA15_110") (pintype "passive"))
    )
    (net (code "75") (name "unconnected-(U2A-PB0-Pad46)") (class "Default")
      (node (ref "U2") (pin "46") (pinfunction "PB0_46") (pintype "passive"))
    )
    (net (code "76") (name "unconnected-(U2A-PB1-Pad47)") (class "Default")
      (node (ref "U2") (pin "47") (pinfunction "PB1_47") (pintype "passive"))
    )
    (net (code "77") (name "unconnected-(U2A-PB2-Pad48)") (class "Default")
      (node (ref "U2") (pin "48") (pinfunction "PB2_48") (pintype "passive"))
    )
    (net (code "78") (name "unconnected-(U2A-PB3-Pad133)") (class "Default")
      (node (ref "U2") (pin "133") (pinfunction "PB3_133") (pintype "bidirectional"))
    )
    (net (code "79") (name "unconnected-(U2A-PB4-Pad134)") (class "Default")
      (node (ref "U2") (pin "134") (pinfunction "PB4_134") (pintype "bidirectional"))
    )
    (net (code "80") (name "unconnected-(U2A-PB5-Pad135)") (class "Default")
      (node (ref "U2") (pin "135") (pinfunction "PB5_135") (pintype "bidirectional"))
    )
    (net (code "81") (name "unconnected-(U2A-PB6-Pad136)") (class "Default")
      (node (ref "U2") (pin "136") (pinfunction "PB6_136") (pintype "bidirectional"))
    )
    (net (code "82") (name "unconnected-(U2A-PB7-Pad137)") (class "Default")
      (node (ref "U2") (pin "137") (pinfunction "PB7_137") (pintype "bidirectional"))
    )
    (net (code "83") (name "unconnected-(U2A-PB8-Pad139)") (class "Default")
      (node (ref "U2") (pin "139") (pinfunction "PB8_139") (pintype "bidirectional"))
    )
    (net (code "84") (name "unconnected-(U2A-PB9-Pad140)") (class "Default")
      (node (ref "U2") (pin "140") (pinfunction "PB9_140") (pintype "bidirectional"))
    )
    (net (code "85") (name "unconnected-(U2A-PB10-Pad69)") (class "Default")
      (node (ref "U2") (pin "69") (pinfunction "PB10_69") (pintype "passive"))
    )
    (net (code "86") (name "unconnected-(U2A-PB11-Pad70)") (class "Default")
      (node (ref "U2") (pin "70") (pinfunction "PB11_70") (pintype "passive"))
    )
    (net (code "87") (name "unconnected-(U2A-PB12-Pad73)") (class "Default")
      (node (ref "U2") (pin "73") (pinfunction "PB12_73") (pintype "passive"))
    )
    (net (code "88") (name "unconnected-(U2A-PB13-Pad74)") (class "Default")
      (node (ref "U2") (pin "74") (pinfunction "PB13_74") (pintype "passive"))
    )
    (net (code "89") (name "unconnected-(U2A-PB14-Pad75)") (class "Default")
      (node (ref "U2") (pin "75") (pinfunction "PB14_75") (pintype "passive"))
    )
    (net (code "90") (name "unconnected-(U2A-PB15-Pad76)") (class "Default")
      (node (ref "U2") (pin "76") (pinfunction "PB15_76") (pintype "passive"))
    )
    (net (code "91") (name "unconnected-(U2A-PC0-Pad26)") (class "Default")
      (node (ref "U2") (pin "26") (pinfunction "PC0_26") (pintype "passive"))
    )
    (net (code "92") (name "unconnected-(U2A-PC9-Pad99)") (class "Default")
      (node (ref "U2") (pin "99") (pinfunction "PC9_99") (pintype "passive"))
    )
    (net (code "93") (name "unconnected-(U2A-PC10-Pad111)") (class "Default")
      (node (ref "U2") (pin "111") (pinfunction "PC10_111") (pintype "passive"))
    )
    (net (code "94") (name "unconnected-(U2A-PC11-Pad112)") (class "Default")
      (node (ref "U2") (pin "112") (pinfunction "PC11_112") (pintype "passive"))
    )
    (net (code "95") (name "unconnected-(U2A-PC12-Pad113)") (class "Default")
      (node (ref "U2") (pin "113") (pinfunction "PC12_113") (pintype "passive"))
    )
    (net (code "96") (name "unconnected-(U2A-PC13-Pad7)") (class "Default")
      (node (ref "U2") (pin "7") (pinfunction "PC13_7") (pintype "passive"))
    )
    (net (code "97") (name "unconnected-(U2A-PC14-Pad8)") (class "Default")
      (node (ref "U2") (pin "8") (pinfunction "PC14_8") (pintype "passive"))
    )
    (net (code "98") (name "unconnected-(U2A-PC15-Pad9)") (class "Default")
      (node (ref "U2") (pin "9") (pinfunction "PC15_9") (pintype "passive"))
    )
    (net (code "99") (name "unconnected-(U2A-PD0-Pad114)") (class "Default")
      (node (ref "U2") (pin "114") (pinfunction "PD0_114") (pintype "passive"))
    )
    (net (code "100") (name "unconnected-(U2A-PD1-Pad115)") (class "Default")
      (node (ref "U2") (pin "115") (pinfunction "PD1_115") (pintype "passive"))
    )
    (net (code "101") (name "unconnected-(U2A-PD2-Pad116)") (class "Default")
      (node (ref "U2") (pin "116") (pinfunction "PD2_116") (pintype "passive"))
    )
    (net (code "102") (name "unconnected-(U2A-PD3-Pad117)") (class "Default")
      (node (ref "U2") (pin "117") (pinfunction "PD3_117") (pintype "passive"))
    )
    (net (code "103") (name "unconnected-(U2A-PD4-Pad118)") (class "Default")
      (node (ref "U2") (pin "118") (pinfunction "PD4_118") (pintype "passive"))
    )
    (net (code "104") (name "unconnected-(U2A-PD5-Pad119)") (class "Default")
      (node (ref "U2") (pin "119") (pinfunction "PD5_119") (pintype "passive"))
    )
    (net (code "105") (name "unconnected-(U2A-PD6-Pad122)") (class "Default")
      (node (ref "U2") (pin "122") (pinfunction "PD6_122") (pintype "passive"))
    )
    (net (code "106") (name "unconnected-(U2A-PD7-Pad123)") (class "Default")
      (node (ref "U2") (pin "123") (pinfunction "PD7_123") (pintype "passive"))
    )
    (net (code "107") (name "unconnected-(U2A-PD8-Pad77)") (class "Default")
      (node (ref "U2") (pin "77") (pinfunction "PD8_77") (pintype "passive"))
    )
    (net (code "108") (name "unconnected-(U2A-PD9-Pad78)") (class "Default")
      (node (ref "U2") (pin "78") (pinfunction "PD9_78") (pintype "passive"))
    )
    (net (code "109") (name "unconnected-(U2A-PD10-Pad79)") (class "Default")
      (node (ref "U2") (pin "79") (pinfunction "PD10_79") (pintype "passive"))
    )
    (net (code "110") (name "unconnected-(U2A-PD11-Pad80)") (class "Default")
      (node (ref "U2") (pin "80") (pinfunction "PD11_80") (pintype "passive"))
    )
    (net (code "111") (name "unconnected-(U2A-PD12-Pad81)") (class "Default")
      (node (ref "U2") (pin "81") (pinfunction "PD12_81") (pintype "passive"))
    )
    (net (code "112") (name "unconnected-(U2A-PD13-Pad82)") (class "Default")
      (node (ref "U2") (pin "82") (pinfunction "PD13_82") (pintype "passive"))
    )
    (net (code "113") (name "unconnected-(U2A-PD14-Pad85)") (class "Default")
      (node (ref "U2") (pin "85") (pinfunction "PD14_85") (pintype "passive"))
    )
    (net (code "114") (name "unconnected-(U2A-PD15-Pad86)") (class "Default")
      (node (ref "U2") (pin "86") (pinfunction "PD15_86") (pintype "passive"))
    )
  )
)
